# receiver.net
KiCad netlist of a schematic drawn in EAGLE
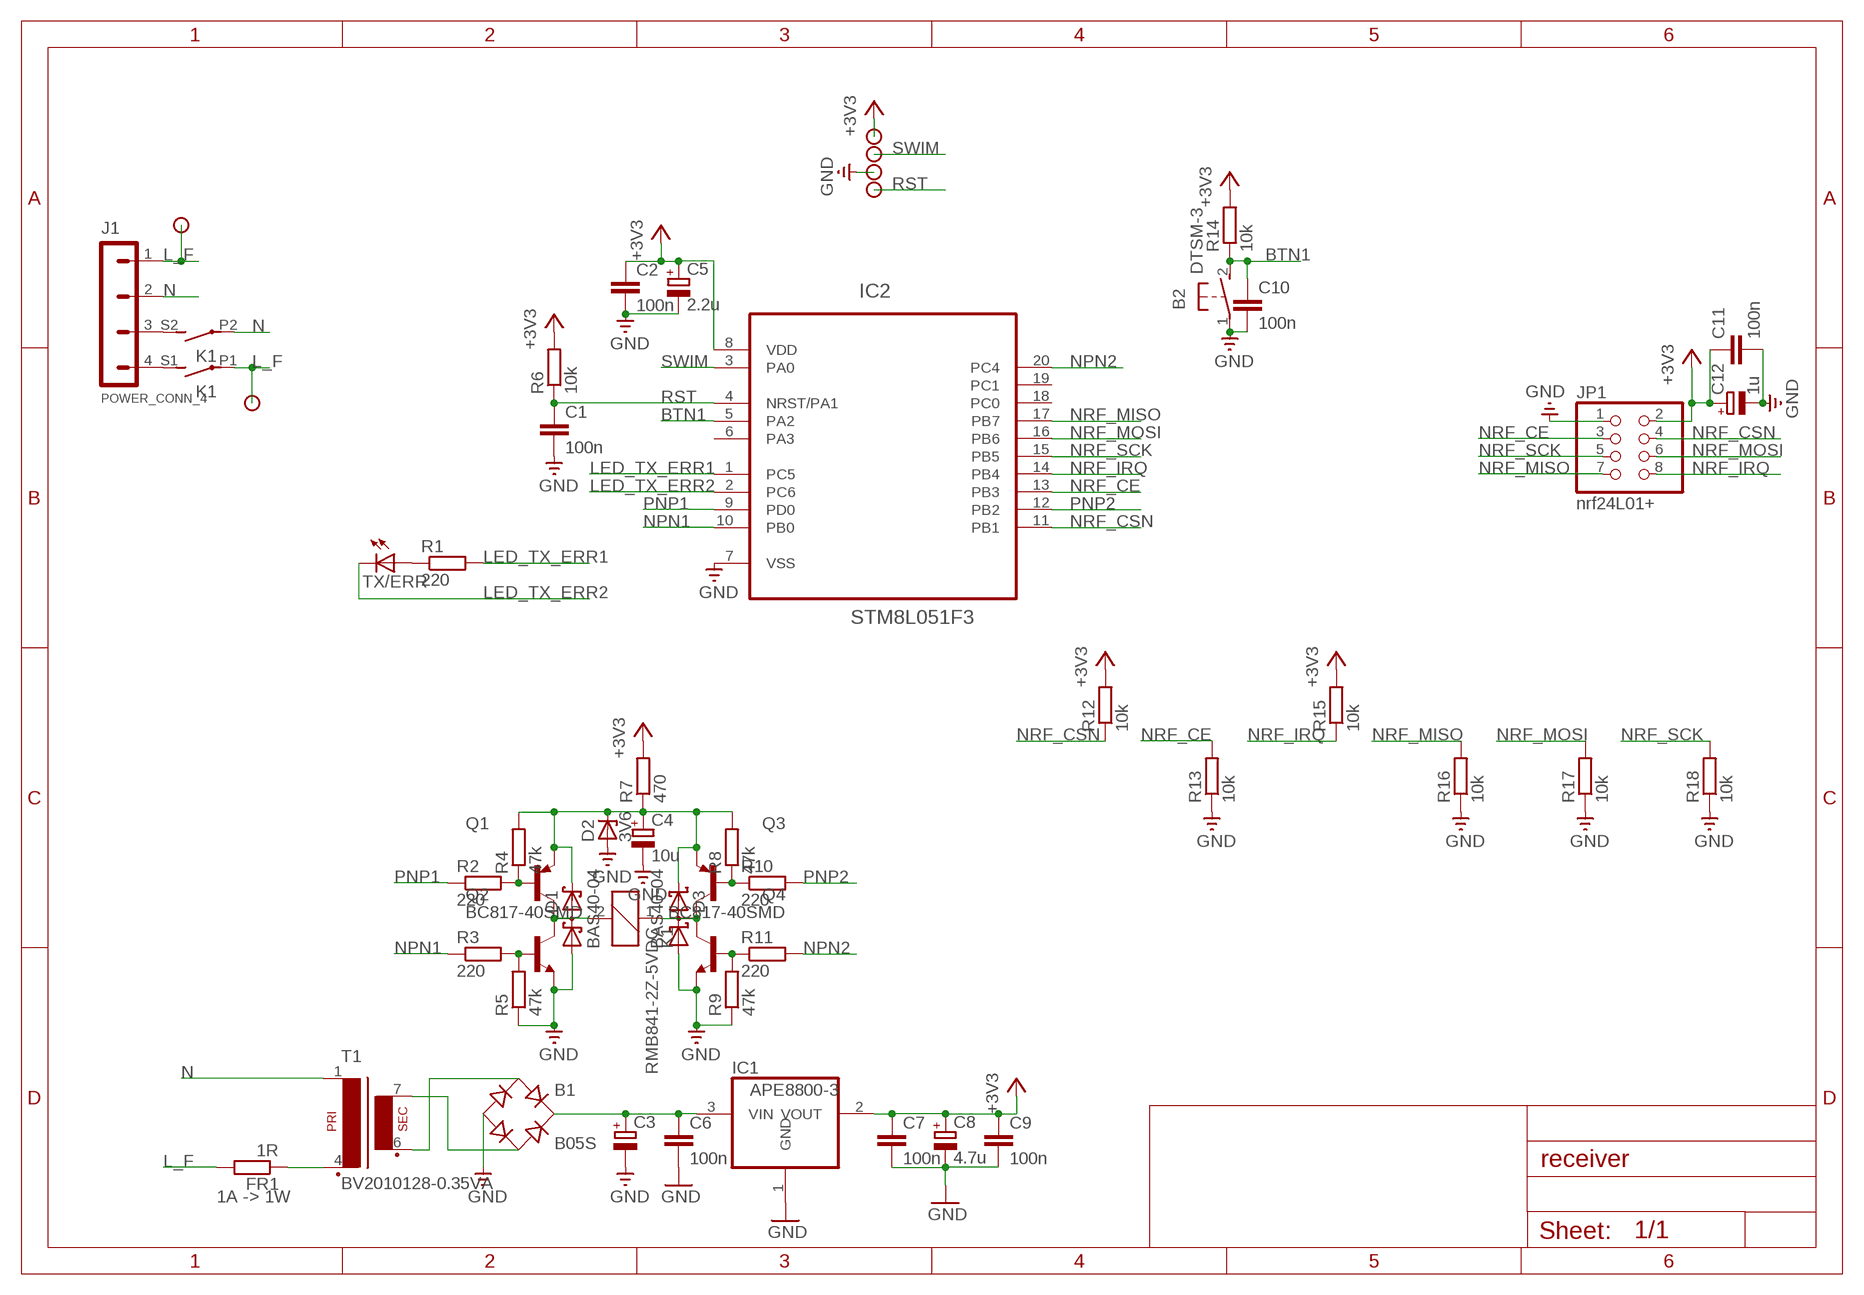
[diagram p0: schematic, sheet 1]

(export (version "E")
  (design (tool "Eeschema 10.0.6"))
  (components
    (comp (ref "B1")
      (value "B05S")
      (footprint "eagle-import:MBS")
      (libsource (lib "eagle-import") (part "BS05"))
    )
    (comp (ref "B2")
      (value "DTSM-3")
      (footprint "eagle-import:DTSM-3")
      (libsource (lib "eagle-import") (part "DTSM-3"))
    )
    (comp (ref "C1")
      (value "100n")
      (footprint "eagle-import:C0603K")
      (libsource (lib "eagle-import") (part "C-EUC0603K"))
    )
    (comp (ref "C2")
      (value "100n")
      (footprint "eagle-import:C0603K")
      (libsource (lib "eagle-import") (part "C-EUC0603K"))
    )
    (comp (ref "C3")
      (value "CPOL-EUSMCB")
      (footprint "eagle-import:SMC_B")
      (libsource (lib "eagle-import") (part "CPOL-EUSMCB"))
    )
    (comp (ref "C4")
      (value "10u")
      (footprint "eagle-import:SMC_B")
      (libsource (lib "eagle-import") (part "CPOL-EUSMCB"))
    )
    (comp (ref "C5")
      (value "2.2u")
      (footprint "eagle-import:SMC_A")
      (libsource (lib "eagle-import") (part "CPOL-EUSMCA"))
    )
    (comp (ref "C6")
      (value "100n")
      (footprint "eagle-import:C0603K")
      (libsource (lib "eagle-import") (part "C-EUC0603K"))
    )
    (comp (ref "C7")
      (value "100n")
      (footprint "eagle-import:C0603K")
      (libsource (lib "eagle-import") (part "C-EUC0603K"))
    )
    (comp (ref "C8")
      (value "4.7u")
      (footprint "eagle-import:SMC_A")
      (libsource (lib "eagle-import") (part "CPOL-EUSMCA"))
    )
    (comp (ref "C9")
      (value "100n")
      (footprint "eagle-import:C0603K")
      (libsource (lib "eagle-import") (part "C-EUC0603K"))
    )
    (comp (ref "C10")
      (value "100n")
      (footprint "eagle-import:C0603K")
      (libsource (lib "eagle-import") (part "C-EUC0603K"))
    )
    (comp (ref "C11")
      (value "100n")
      (footprint "eagle-import:C0603K")
      (libsource (lib "eagle-import") (part "C-EUC0603K"))
    )
    (comp (ref "C12")
      (value "1u")
      (footprint "eagle-import:SMC_A")
      (libsource (lib "eagle-import") (part "CPOL-EUSMCA"))
    )
    (comp (ref "D1")
      (value "BAS40-04")
      (footprint "eagle-import:SOT23")
      (libsource (lib "eagle-import") (part "BAS40-04"))
    )
    (comp (ref "D2")
      (value "3V6")
      (footprint "eagle-import:SOT23")
      (libsource (lib "eagle-import") (part "ZENER-DIODESOT23"))
    )
    (comp (ref "D3")
      (value "BAS40-04")
      (footprint "eagle-import:SOT23")
      (libsource (lib "eagle-import") (part "BAS40-04"))
    )
    (comp (ref "FR1")
      (value "1R")
      (footprint "eagle-import:0309_10")
      (libsource (lib "eagle-import") (part "R-EU_0309/10"))
    )
    (comp (ref "IC1")
      (value "APE8800-3")
      (footprint "eagle-import:SOT23")
      (libsource (lib "eagle-import") (part "APE8800-3"))
    )
    (comp (ref "IC2")
      (value "STM8L051F3")
      (footprint "eagle-import:TSSOP20")
      (libsource (lib "eagle-import") (part "STM8L051F3"))
    )
    (comp (ref "J1")
      (value "POWER_CONN_4")
      (footprint "eagle-import:TERMINAL_BLOCK_4")
      (libsource (lib "eagle-import") (part "POWER_CONN_4"))
    )
    (comp (ref "J2")
      (value "CON_PAD_THICK_WIRE")
      (footprint "eagle-import:SMD_PAD_THICK_WIRE")
      (libsource (lib "eagle-import") (part "CON_PAD_THICK_WIRE"))
    )
    (comp (ref "J3")
      (value "CON_PAD_THICK_WIRE")
      (footprint "eagle-import:SMD_PAD_THICK_WIRE")
      (libsource (lib "eagle-import") (part "CON_PAD_THICK_WIRE"))
    )
    (comp (ref "JP1")
      (value "nrf24L01+")
      (footprint "eagle-import:2X04")
      (libsource (lib "eagle-import") (part "PINHD-2X4"))
    )
    (comp (ref "K1")
      (value "RMB841-2Z-5VDC")
      (footprint "eagle-import:RMB841-2Z-5VDC")
      (libsource (lib "eagle-import") (part "RMB841-2Z-5VDC"))
    )
    (comp (ref "Q1")
      (value "BC807-40-PNP-SOT23-BEC")
      (footprint "eagle-import:SOT23-BEC")
      (libsource (lib "eagle-import") (part "-PNP-SOT23-BECBC807-40"))
    )
    (comp (ref "Q2")
      (value "BC817-40SMD")
      (footprint "eagle-import:SOT23-BEC")
      (libsource (lib "eagle-import") (part "BC817SMD-40"))
    )
    (comp (ref "Q3")
      (value "BC807-40-PNP-SOT23-BEC")
      (footprint "eagle-import:SOT23-BEC")
      (libsource (lib "eagle-import") (part "-PNP-SOT23-BECBC807-40"))
    )
    (comp (ref "Q4")
      (value "BC817-40SMD")
      (footprint "eagle-import:SOT23-BEC")
      (libsource (lib "eagle-import") (part "BC817SMD-40"))
    )
    (comp (ref "R1")
      (value "220")
      (footprint "eagle-import:R0603")
      (libsource (lib "eagle-import") (part "R-EU_R0603"))
    )
    (comp (ref "R2")
      (value "220")
      (footprint "eagle-import:R0603")
      (libsource (lib "eagle-import") (part "R-EU_R0603"))
    )
    (comp (ref "R3")
      (value "220")
      (footprint "eagle-import:R0603")
      (libsource (lib "eagle-import") (part "R-EU_R0603"))
    )
    (comp (ref "R4")
      (value "47k")
      (footprint "eagle-import:R0603")
      (libsource (lib "eagle-import") (part "R-EU_R0603"))
    )
    (comp (ref "R5")
      (value "47k")
      (footprint "eagle-import:R0603")
      (libsource (lib "eagle-import") (part "R-EU_R0603"))
    )
    (comp (ref "R6")
      (value "10k")
      (footprint "eagle-import:R0603")
      (libsource (lib "eagle-import") (part "R-EU_R0603"))
    )
    (comp (ref "R7")
      (value "470")
      (footprint "eagle-import:R0603")
      (libsource (lib "eagle-import") (part "R-EU_R0603"))
    )
    (comp (ref "R8")
      (value "47k")
      (footprint "eagle-import:R0603")
      (libsource (lib "eagle-import") (part "R-EU_R0603"))
    )
    (comp (ref "R9")
      (value "47k")
      (footprint "eagle-import:R0603")
      (libsource (lib "eagle-import") (part "R-EU_R0603"))
    )
    (comp (ref "R10")
      (value "220")
      (footprint "eagle-import:R0603")
      (libsource (lib "eagle-import") (part "R-EU_R0603"))
    )
    (comp (ref "R11")
      (value "220")
      (footprint "eagle-import:R0603")
      (libsource (lib "eagle-import") (part "R-EU_R0603"))
    )
    (comp (ref "R12")
      (value "10k")
      (footprint "eagle-import:R0603")
      (libsource (lib "eagle-import") (part "R-EU_R0603"))
    )
    (comp (ref "R13")
      (value "10k")
      (footprint "eagle-import:R0603")
      (libsource (lib "eagle-import") (part "R-EU_R0603"))
    )
    (comp (ref "R14")
      (value "10k")
      (footprint "eagle-import:R0603")
      (libsource (lib "eagle-import") (part "R-EU_R0603"))
    )
    (comp (ref "R15")
      (value "10k")
      (footprint "eagle-import:R0603")
      (libsource (lib "eagle-import") (part "R-EU_R0603"))
    )
    (comp (ref "R16")
      (value "10k")
      (footprint "eagle-import:R0603")
      (libsource (lib "eagle-import") (part "R-EU_R0603"))
    )
    (comp (ref "R17")
      (value "10k")
      (footprint "eagle-import:R0603")
      (libsource (lib "eagle-import") (part "R-EU_R0603"))
    )
    (comp (ref "R18")
      (value "10k")
      (footprint "eagle-import:R0603")
      (libsource (lib "eagle-import") (part "R-EU_R0603"))
    )
    (comp (ref "SIG_+3V1")
      (value "CON_PAD")
      (footprint "eagle-import:SMD_PAD")
      (libsource (lib "eagle-import") (part "CON_PAD"))
    )
    (comp (ref "SIG_GND")
      (value "CON_PAD")
      (footprint "eagle-import:SMD_PAD")
      (libsource (lib "eagle-import") (part "CON_PAD"))
    )
    (comp (ref "SIG_RST")
      (value "CON_PAD")
      (footprint "eagle-import:SMD_PAD")
      (libsource (lib "eagle-import") (part "CON_PAD"))
    )
    (comp (ref "SIG_SWIM")
      (value "CON_PAD")
      (footprint "eagle-import:SMD_PAD")
      (libsource (lib "eagle-import") (part "CON_PAD"))
    )
    (comp (ref "T1")
      (value "BV2010128-0.35VA")
      (footprint "eagle-import:BV2010128-0.35VA")
      (libsource (lib "eagle-import") (part "BV2010128-0.35VA"))
    )
    (comp (ref "TX/ERR")
      (value "LED3MM")
      (footprint "eagle-import:LED3MM")
      (libsource (lib "eagle-import") (part "LED3MM"))
    )
  )
  (nets
    (net (code "1") (name "+3V3") (class "Default")
      (node (ref "C11") (pin "1") (pinfunction "1_1") (pintype "passive"))
      (node (ref "C12") (pin "+") (pinfunction "+_+") (pintype "passive"))
      (node (ref "C2") (pin "1") (pinfunction "1_1") (pintype "passive"))
      (node (ref "C5") (pin "+") (pinfunction "+_+") (pintype "passive"))
      (node (ref "C7") (pin "1") (pinfunction "1_1") (pintype "passive"))
      (node (ref "C8") (pin "+") (pinfunction "+_+") (pintype "passive"))
      (node (ref "C9") (pin "1") (pinfunction "1_1") (pintype "passive"))
      (node (ref "IC1") (pin "2") (pinfunction "VOUT_2") (pintype "output"))
      (node (ref "IC2") (pin "8") (pinfunction "VDD_8") (pintype "power_in"))
      (node (ref "JP1") (pin "2") (pinfunction "2_2") (pintype "passive"))
      (node (ref "R12") (pin "2") (pinfunction "2_2") (pintype "passive"))
      (node (ref "R14") (pin "2") (pinfunction "2_2") (pintype "passive"))
      (node (ref "R15") (pin "2") (pinfunction "2_2") (pintype "passive"))
      (node (ref "R6") (pin "2") (pinfunction "2_2") (pintype "passive"))
      (node (ref "R7") (pin "2") (pinfunction "2_2") (pintype "passive"))
      (node (ref "SIG_+3V1") (pin "P$1") (pinfunction "P$1_P$1") (pintype "bidirectional"))
    )
    (net (code "2") (name "/BTN1") (class "Default")
      (node (ref "B2") (pin "2") (pinfunction "2_2") (pintype "passive"))
      (node (ref "C10") (pin "1") (pinfunction "1_1") (pintype "passive"))
      (node (ref "IC2") (pin "5") (pinfunction "PA2_5") (pintype "bidirectional"))
      (node (ref "R14") (pin "1") (pinfunction "1_1") (pintype "passive"))
    )
    (net (code "3") (name "/LED_TX_ERR1") (class "Default")
      (node (ref "IC2") (pin "1") (pinfunction "PC5_1") (pintype "bidirectional"))
      (node (ref "R1") (pin "2") (pinfunction "2_2") (pintype "passive"))
    )
    (net (code "4") (name "/LED_TX_ERR2") (class "Default")
      (node (ref "IC2") (pin "2") (pinfunction "PC6_2") (pintype "bidirectional"))
      (node (ref "TX/ERR") (pin "K") (pinfunction "C_K") (pintype "passive"))
    )
    (net (code "5") (name "/L_F") (class "Default")
      (node (ref "FR1") (pin "2") (pinfunction "2_2") (pintype "passive"))
      (node (ref "J1") (pin "1") (pinfunction "P$1_1") (pintype "bidirectional"))
      (node (ref "J2") (pin "P$1") (pinfunction "P$1_P$1") (pintype "bidirectional"))
      (node (ref "J3") (pin "P$1") (pinfunction "P$1_P$1") (pintype "bidirectional"))
      (node (ref "K1") (pin "P1") (pinfunction "P_P1") (pintype "passive"))
    )
    (net (code "6") (name "/N") (class "Default")
      (node (ref "J1") (pin "2") (pinfunction "P$2_2") (pintype "bidirectional"))
      (node (ref "K1") (pin "P2") (pinfunction "P_P2") (pintype "passive"))
      (node (ref "T1") (pin "1") (pinfunction "P1_1") (pintype "passive"))
    )
    (net (code "7") (name "/NPN1") (class "Default")
      (node (ref "IC2") (pin "10") (pinfunction "PB0_10") (pintype "bidirectional"))
      (node (ref "R3") (pin "1") (pinfunction "1_1") (pintype "passive"))
    )
    (net (code "8") (name "/NPN2") (class "Default")
      (node (ref "IC2") (pin "20") (pinfunction "PC4_20") (pintype "bidirectional"))
      (node (ref "R11") (pin "2") (pinfunction "2_2") (pintype "passive"))
    )
    (net (code "9") (name "/NRF_CE") (class "Default")
      (node (ref "IC2") (pin "13") (pinfunction "PB3_13") (pintype "bidirectional"))
      (node (ref "JP1") (pin "3") (pinfunction "3_3") (pintype "passive"))
      (node (ref "R13") (pin "2") (pinfunction "2_2") (pintype "passive"))
    )
    (net (code "10") (name "/NRF_CSN") (class "Default")
      (node (ref "IC2") (pin "11") (pinfunction "PB1_11") (pintype "bidirectional"))
      (node (ref "JP1") (pin "4") (pinfunction "4_4") (pintype "passive"))
      (node (ref "R12") (pin "1") (pinfunction "1_1") (pintype "passive"))
    )
    (net (code "11") (name "/NRF_IRQ") (class "Default")
      (node (ref "IC2") (pin "14") (pinfunction "PB4_14") (pintype "bidirectional"))
      (node (ref "JP1") (pin "8") (pinfunction "8_8") (pintype "passive"))
      (node (ref "R15") (pin "1") (pinfunction "1_1") (pintype "passive"))
    )
    (net (code "12") (name "/NRF_MISO") (class "Default")
      (node (ref "IC2") (pin "17") (pinfunction "PB7_17") (pintype "bidirectional"))
      (node (ref "JP1") (pin "7") (pinfunction "7_7") (pintype "passive"))
      (node (ref "R16") (pin "2") (pinfunction "2_2") (pintype "passive"))
    )
    (net (code "13") (name "/NRF_MOSI") (class "Default")
      (node (ref "IC2") (pin "16") (pinfunction "PB6_16") (pintype "bidirectional"))
      (node (ref "JP1") (pin "6") (pinfunction "6_6") (pintype "passive"))
      (node (ref "R17") (pin "2") (pinfunction "2_2") (pintype "passive"))
    )
    (net (code "14") (name "/NRF_SCK") (class "Default")
      (node (ref "IC2") (pin "15") (pinfunction "PB5_15") (pintype "bidirectional"))
      (node (ref "JP1") (pin "5") (pinfunction "5_5") (pintype "passive"))
      (node (ref "R18") (pin "2") (pinfunction "2_2") (pintype "passive"))
    )
    (net (code "15") (name "/PNP1") (class "Default")
      (node (ref "IC2") (pin "9") (pinfunction "PD0_9") (pintype "bidirectional"))
      (node (ref "R2") (pin "1") (pinfunction "1_1") (pintype "passive"))
    )
    (net (code "16") (name "/PNP2") (class "Default")
      (node (ref "IC2") (pin "12") (pinfunction "PB2_12") (pintype "bidirectional"))
      (node (ref "R10") (pin "2") (pinfunction "2_2") (pintype "passive"))
    )
    (net (code "17") (name "/RST") (class "Default")
      (node (ref "C1") (pin "1") (pinfunction "1_1") (pintype "passive"))
      (node (ref "IC2") (pin "4") (pinfunction "NRST/PA1_4") (pintype "bidirectional"))
      (node (ref "R6") (pin "1") (pinfunction "1_1") (pintype "passive"))
      (node (ref "SIG_RST") (pin "P$1") (pinfunction "P$1_P$1") (pintype "bidirectional"))
    )
    (net (code "18") (name "/SWIM") (class "Default")
      (node (ref "IC2") (pin "3") (pinfunction "PA0_3") (pintype "power_in"))
      (node (ref "SIG_SWIM") (pin "P$1") (pinfunction "P$1_P$1") (pintype "bidirectional"))
    )
    (net (code "19") (name "GND") (class "Default")
      (node (ref "B1") (pin "-") (pinfunction "-_-") (pintype "passive"))
      (node (ref "B2") (pin "1") (pinfunction "1_1") (pintype "passive"))
      (node (ref "C1") (pin "2") (pinfunction "2_2") (pintype "passive"))
      (node (ref "C10") (pin "2") (pinfunction "2_2") (pintype "passive"))
      (node (ref "C11") (pin "2") (pinfunction "2_2") (pintype "passive"))
      (node (ref "C12") (pin "-") (pinfunction "-_-") (pintype "passive"))
      (node (ref "C2") (pin "2") (pinfunction "2_2") (pintype "passive"))
      (node (ref "C3") (pin "-") (pinfunction "-_-") (pintype "passive"))
      (node (ref "C4") (pin "-") (pinfunction "-_-") (pintype "passive"))
      (node (ref "C5") (pin "-") (pinfunction "-_-") (pintype "passive"))
      (node (ref "C6") (pin "2") (pinfunction "2_2") (pintype "passive"))
      (node (ref "C7") (pin "2") (pinfunction "2_2") (pintype "passive"))
      (node (ref "C8") (pin "-") (pinfunction "-_-") (pintype "passive"))
      (node (ref "C9") (pin "2") (pinfunction "2_2") (pintype "passive"))
      (node (ref "D1") (pin "1") (pinfunction "A1_1") (pintype "passive"))
      (node (ref "D2") (pin "1") (pinfunction "A_1") (pintype "passive"))
      (node (ref "D3") (pin "1") (pinfunction "A1_1") (pintype "passive"))
      (node (ref "IC1") (pin "1") (pinfunction "GND_1") (pintype "power_in"))
      (node (ref "IC2") (pin "7") (pinfunction "VSS_7") (pintype "power_in"))
      (node (ref "JP1") (pin "1") (pinfunction "1_1") (pintype "passive"))
      (node (ref "Q2") (pin "E") (pinfunction "E_E") (pintype "passive"))
      (node (ref "Q4") (pin "E") (pinfunction "E_E") (pintype "passive"))
      (node (ref "R13") (pin "1") (pinfunction "1_1") (pintype "passive"))
      (node (ref "R16") (pin "1") (pinfunction "1_1") (pintype "passive"))
      (node (ref "R17") (pin "1") (pinfunction "1_1") (pintype "passive"))
      (node (ref "R18") (pin "1") (pinfunction "1_1") (pintype "passive"))
      (node (ref "R5") (pin "1") (pinfunction "1_1") (pintype "passive"))
      (node (ref "R9") (pin "1") (pinfunction "1_1") (pintype "passive"))
      (node (ref "SIG_GND") (pin "P$1") (pinfunction "P$1_P$1") (pintype "bidirectional"))
    )
    (net (code "20") (name "Net-(D1-C1A2)") (class "Default")
      (node (ref "D1") (pin "3") (pinfunction "C1A2_3") (pintype "passive"))
      (node (ref "K1") (pin "2") (pinfunction "2_2") (pintype "passive"))
      (node (ref "Q1") (pin "C") (pinfunction "C_C") (pintype "passive"))
      (node (ref "Q2") (pin "C") (pinfunction "C_C") (pintype "passive"))
    )
    (net (code "21") (name "Net-(D1-C2)") (class "Default")
      (node (ref "C4") (pin "+") (pinfunction "+_+") (pintype "passive"))
      (node (ref "D1") (pin "2") (pinfunction "C2_2") (pintype "passive"))
      (node (ref "D2") (pin "3") (pinfunction "C_3") (pintype "passive"))
      (node (ref "D3") (pin "2") (pinfunction "C2_2") (pintype "passive"))
      (node (ref "Q1") (pin "E") (pinfunction "E_E") (pintype "passive"))
      (node (ref "Q3") (pin "E") (pinfunction "E_E") (pintype "passive"))
      (node (ref "R4") (pin "2") (pinfunction "2_2") (pintype "passive"))
      (node (ref "R7") (pin "1") (pinfunction "1_1") (pintype "passive"))
      (node (ref "R8") (pin "2") (pinfunction "2_2") (pintype "passive"))
    )
    (net (code "22") (name "Net-(D3-C1A2)") (class "Default")
      (node (ref "D3") (pin "3") (pinfunction "C1A2_3") (pintype "passive"))
      (node (ref "K1") (pin "1") (pinfunction "1_1") (pintype "passive"))
      (node (ref "Q3") (pin "C") (pinfunction "C_C") (pintype "passive"))
      (node (ref "Q4") (pin "C") (pinfunction "C_C") (pintype "passive"))
    )
    (net (code "23") (name "Net-(IC1-VIN)") (class "Default")
      (node (ref "B1") (pin "+") (pinfunction "+_+") (pintype "passive"))
      (node (ref "C3") (pin "+") (pinfunction "+_+") (pintype "passive"))
      (node (ref "C6") (pin "1") (pinfunction "1_1") (pintype "passive"))
      (node (ref "IC1") (pin "3") (pinfunction "VIN_3") (pintype "input"))
    )
    (net (code "24") (name "Net-(J1-P$3)") (class "Default")
      (node (ref "J1") (pin "3") (pinfunction "P$3_3") (pintype "bidirectional"))
      (node (ref "K1") (pin "S2") (pinfunction "S_S2") (pintype "passive"))
    )
    (net (code "25") (name "Net-(J1-P$4)") (class "Default")
      (node (ref "J1") (pin "4") (pinfunction "P$4_4") (pintype "bidirectional"))
      (node (ref "K1") (pin "S1") (pinfunction "S_S1") (pintype "passive"))
    )
    (net (code "26") (name "Net-(Q1-PadB)") (class "Default")
      (node (ref "Q1") (pin "B") (pinfunction "B_B") (pintype "passive"))
      (node (ref "R2") (pin "2") (pinfunction "2_2") (pintype "passive"))
      (node (ref "R4") (pin "1") (pinfunction "1_1") (pintype "passive"))
    )
    (net (code "27") (name "Net-(Q2-PadB)") (class "Default")
      (node (ref "Q2") (pin "B") (pinfunction "B_B") (pintype "passive"))
      (node (ref "R3") (pin "2") (pinfunction "2_2") (pintype "passive"))
      (node (ref "R5") (pin "2") (pinfunction "2_2") (pintype "passive"))
    )
    (net (code "28") (name "Net-(Q3-PadB)") (class "Default")
      (node (ref "Q3") (pin "B") (pinfunction "B_B") (pintype "passive"))
      (node (ref "R10") (pin "1") (pinfunction "1_1") (pintype "passive"))
      (node (ref "R8") (pin "1") (pinfunction "1_1") (pintype "passive"))
    )
    (net (code "29") (name "Net-(Q4-PadB)") (class "Default")
      (node (ref "Q4") (pin "B") (pinfunction "B_B") (pintype "passive"))
      (node (ref "R11") (pin "1") (pinfunction "1_1") (pintype "passive"))
      (node (ref "R9") (pin "2") (pinfunction "2_2") (pintype "passive"))
    )
    (net (code "30") (name "Net-(R1-Pad1)") (class "Default")
      (node (ref "R1") (pin "1") (pinfunction "1_1") (pintype "passive"))
      (node (ref "TX/ERR") (pin "A") (pinfunction "A_A") (pintype "passive"))
    )
    (net (code "31") (name "Net-(T1-P2)") (class "Default")
      (node (ref "FR1") (pin "1") (pinfunction "1_1") (pintype "passive"))
      (node (ref "T1") (pin "4") (pinfunction "P2_4") (pintype "passive"))
    )
    (net (code "32") (name "Net-(T1-S3)") (class "Default")
      (node (ref "B1") (pin "AC1") (pinfunction "AC1_AC1") (pintype "passive"))
      (node (ref "T1") (pin "6") (pinfunction "S3_6") (pintype "passive"))
    )
    (net (code "33") (name "Net-(T1-S4)") (class "Default")
      (node (ref "B1") (pin "AC2") (pinfunction "AC2_AC2") (pintype "passive"))
      (node (ref "T1") (pin "7") (pinfunction "S4_7") (pintype "passive"))
    )
    (net (code "34") (name "unconnected-(IC2-PA3-Pad6)") (class "Default")
      (node (ref "IC2") (pin "6") (pinfunction "PA3_6") (pintype "bidirectional"))
    )
    (net (code "35") (name "unconnected-(IC2-PC0-Pad18)") (class "Default")
      (node (ref "IC2") (pin "18") (pinfunction "PC0_18") (pintype "bidirectional"))
    )
    (net (code "36") (name "unconnected-(IC2-PC1-Pad19)") (class "Default")
      (node (ref "IC2") (pin "19") (pinfunction "PC1_19") (pintype "bidirectional"))
    )
  )
)
